# Sch_Motor.net
KiCad netlist of a schematic drawn in Altium Designer
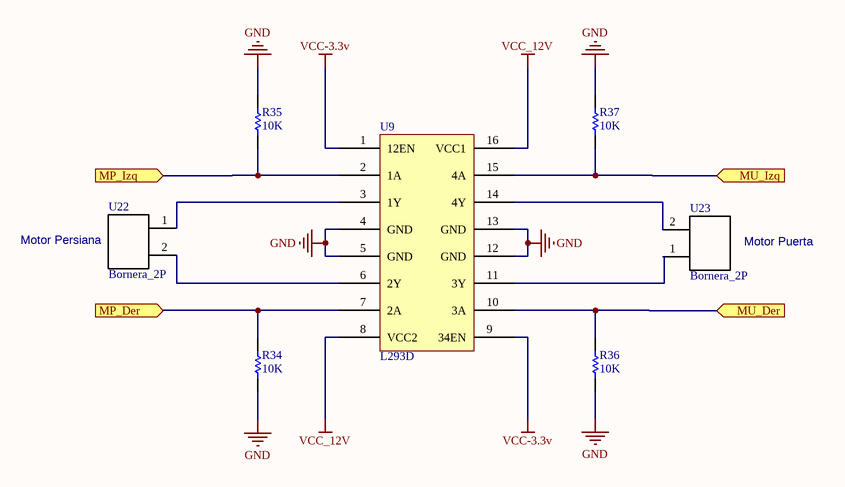
[diagram p0: Sch_Motor.SchDoc]

(export (version "E")
  (design (tool "Eeschema 10.0.6"))
  (components
    (comp (ref "R34")
      (value "10K")
      (footprint "AXIAL-0.3")
      (description "Resistor")
      (fields (field (name "Comment") "Res1") (field (name "PUBLISHER") "Altium Limited"))
      (libsource (lib "Miscellaneous Devices") (part "Res1"))
    )
    (comp (ref "R35")
      (value "10K")
      (footprint "AXIAL-0.3")
      (description "Resistor")
      (fields (field (name "Comment") "Res1") (field (name "PUBLISHER") "Altium Limited"))
      (libsource (lib "Miscellaneous Devices") (part "Res1"))
    )
    (comp (ref "R36")
      (value "10K")
      (footprint "AXIAL-0.3")
      (description "Resistor")
      (fields (field (name "Comment") "Res1") (field (name "PUBLISHER") "Altium Limited"))
      (libsource (lib "Miscellaneous Devices") (part "Res1"))
    )
    (comp (ref "R37")
      (value "10K")
      (footprint "AXIAL-0.3")
      (description "Resistor")
      (fields (field (name "Comment") "Res1") (field (name "PUBLISHER") "Altium Limited"))
      (libsource (lib "Miscellaneous Devices") (part "Res1"))
    )
    (comp (ref "U9")
      (value "L293D")
      (footprint "DIP16")
      (description "Texas Quadruple Half-H Drivers")
      (libsource (lib "Sch_PuenteH") (part "L293D"))
    )
    (comp (ref "U22") (value "Bornera_2P") (footprint "Bornera") (libsource (lib "") (part "Bornera_2P_1")))
    (comp (ref "U23")
      (value "Bornera_2P")
      (footprint "Bornera")
      (libsource (lib "Ampli_Lib_Sch") (part "Bornera_2P"))
    )
  )
  (nets
    (net (code "1") (name "/MP_Der") (class "Default")
      (node (ref "R34") (pin "2") (pinfunction "2_2") (pintype "passive"))
      (node (ref "U9") (pin "7") (pinfunction "2A_7") (pintype "passive"))
    )
    (net (code "2") (name "/MP_Izq") (class "Default")
      (node (ref "R35") (pin "1") (pinfunction "1_1") (pintype "passive"))
      (node (ref "U9") (pin "2") (pinfunction "1A_2") (pintype "passive"))
    )
    (net (code "3") (name "/MU_Der") (class "Default")
      (node (ref "R36") (pin "2") (pinfunction "2_2") (pintype "passive"))
      (node (ref "U9") (pin "10") (pinfunction "3A_10") (pintype "passive"))
    )
    (net (code "4") (name "/MU_Izq") (class "Default")
      (node (ref "R37") (pin "1") (pinfunction "1_1") (pintype "passive"))
      (node (ref "U9") (pin "15") (pinfunction "4A_15") (pintype "passive"))
    )
    (net (code "5") (name "GND") (class "Default")
      (node (ref "R34") (pin "1") (pinfunction "1_1") (pintype "passive"))
      (node (ref "R35") (pin "2") (pinfunction "2_2") (pintype "passive"))
      (node (ref "R36") (pin "1") (pinfunction "1_1") (pintype "passive"))
      (node (ref "R37") (pin "2") (pinfunction "2_2") (pintype "passive"))
      (node (ref "U9") (pin "12") (pinfunction "GND_12") (pintype "passive"))
      (node (ref "U9") (pin "13") (pinfunction "GND_13") (pintype "passive"))
      (node (ref "U9") (pin "4") (pinfunction "GND_4") (pintype "passive"))
      (node (ref "U9") (pin "5") (pinfunction "GND_5") (pintype "passive"))
    )
    (net (code "6") (name "Net-(U9-1Y)") (class "Default")
      (node (ref "U22") (pin "1") (pinfunction "1_1") (pintype "passive"))
      (node (ref "U9") (pin "3") (pinfunction "1Y_3") (pintype "passive"))
    )
    (net (code "7") (name "Net-(U9-2Y)") (class "Default")
      (node (ref "U22") (pin "2") (pinfunction "2_2") (pintype "passive"))
      (node (ref "U9") (pin "6") (pinfunction "2Y_6") (pintype "passive"))
    )
    (net (code "8") (name "Net-(U9-3Y)") (class "Default")
      (node (ref "U23") (pin "1") (pinfunction "1_1") (pintype "passive"))
      (node (ref "U9") (pin "11") (pinfunction "3Y_11") (pintype "passive"))
    )
    (net (code "9") (name "Net-(U9-4Y)") (class "Default")
      (node (ref "U23") (pin "2") (pinfunction "2_2") (pintype "passive"))
      (node (ref "U9") (pin "14") (pinfunction "4Y_14") (pintype "passive"))
    )
    (net (code "10") (name "VCC-3.3v") (class "Default")
      (node (ref "U9") (pin "1") (pinfunction "12EN_1") (pintype "passive"))
      (node (ref "U9") (pin "9") (pinfunction "34EN_9") (pintype "passive"))
    )
    (net (code "11") (name "VCC_12V") (class "Default")
      (node (ref "U9") (pin "16") (pinfunction "VCC1_16") (pintype "passive"))
      (node (ref "U9") (pin "8") (pinfunction "VCC2_8") (pintype "passive"))
    )
  )
)
